# 485Driver_MAX3462.net
KiCad netlist of a schematic drawn in Altium Designer
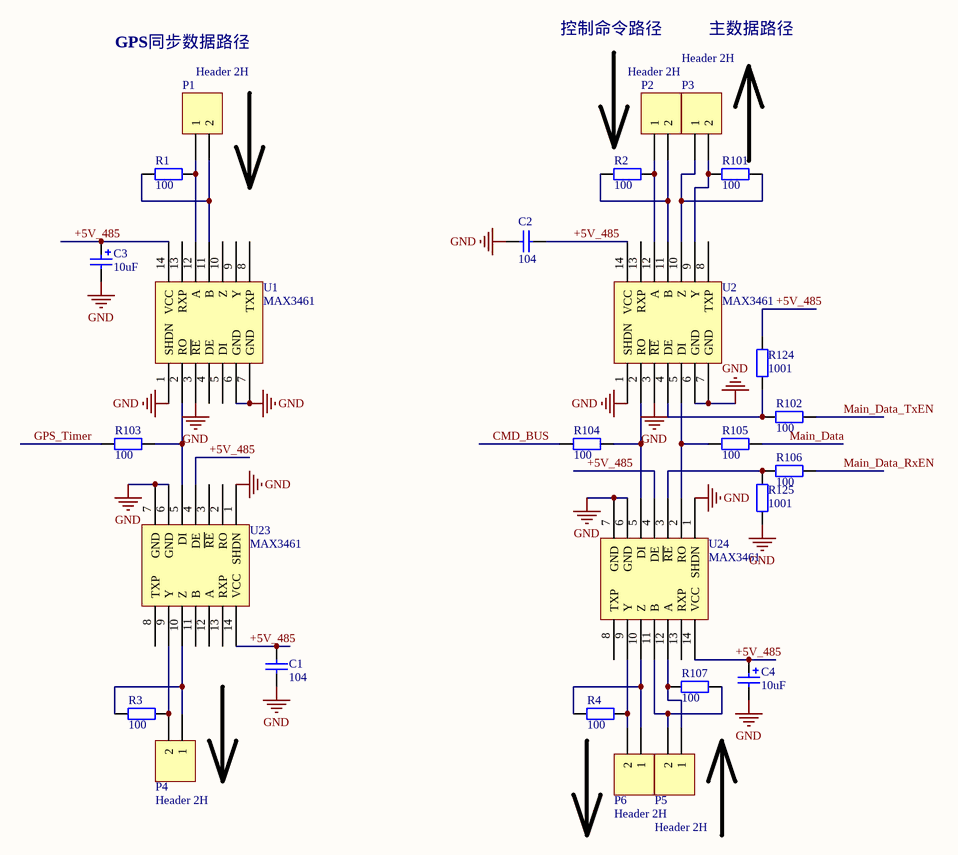
[diagram p0: 485Driver_MAX3462.SchDoc]

(export (version "E")
  (design (tool "Eeschema 10.0.6"))
  (components
    (comp (ref "C1")
      (value "104")
      (footprint "0805C")
      (description "Capacitor")
      (fields (field (name "PUBLISHER") "Altium Limited"))
      (libsource (lib "Miscellaneous Devices") (part "Cap"))
    )
    (comp (ref "C2")
      (value "104")
      (footprint "0805C")
      (description "Capacitor")
      (fields (field (name "PUBLISHER") "Altium Limited"))
      (libsource (lib "Miscellaneous Devices") (part "Cap"))
    )
    (comp (ref "C3")
      (value "10uF")
      (footprint "C68uF")
      (description "Polarized Capacitor (Axial)")
      (fields (field (name "PUBLISHER") "Altium Limited"))
      (libsource (lib "Miscellaneous Devices") (part "Cap Pol2"))
    )
    (comp (ref "C4")
      (value "10uF")
      (footprint "C68uF")
      (description "Polarized Capacitor (Axial)")
      (fields (field (name "PUBLISHER") "Altium Limited"))
      (libsource (lib "Miscellaneous Devices") (part "Cap Pol2"))
    )
    (comp (ref "P1")
      (value "Header 2H")
      (footprint "HDR1X2")
      (description "Header, 2-Pin, Right Angle")
      (fields (field (name "PUBLISHER") "Altium Limited"))
      (libsource (lib "Miscellaneous Connectors") (part "Header 2H"))
    )
    (comp (ref "P2")
      (value "Header 2H")
      (footprint "HDR1X2")
      (description "Header, 2-Pin, Right Angle")
      (fields (field (name "PUBLISHER") "Altium Limited"))
      (libsource (lib "Miscellaneous Connectors") (part "Header 2H"))
    )
    (comp (ref "P3")
      (value "Header 2H")
      (footprint "HDR1X2")
      (description "Header, 2-Pin, Right Angle")
      (fields (field (name "PUBLISHER") "Altium Limited"))
      (libsource (lib "Miscellaneous Connectors") (part "Header 2H"))
    )
    (comp (ref "P4")
      (value "Header 2H")
      (footprint "HDR1X2")
      (description "Header, 2-Pin, Right Angle")
      (fields (field (name "PUBLISHER") "Altium Limited"))
      (libsource (lib "") (part "Header 2H_1"))
    )
    (comp (ref "P5")
      (value "Header 2H")
      (footprint "HDR1X2")
      (description "Header, 2-Pin, Right Angle")
      (fields (field (name "PUBLISHER") "Altium Limited"))
      (libsource (lib "") (part "Header 2H_1"))
    )
    (comp (ref "P6")
      (value "Header 2H")
      (footprint "HDR1X2")
      (description "Header, 2-Pin, Right Angle")
      (fields (field (name "PUBLISHER") "Altium Limited"))
      (libsource (lib "") (part "Header 2H_1"))
    )
    (comp (ref "R1")
      (value "100")
      (footprint "0805R")
      (description "Resistor")
      (fields (field (name "PUBLISHER") "Altium Limited"))
      (libsource (lib "") (part "Res2_1"))
    )
    (comp (ref "R2")
      (value "100")
      (footprint "0805R")
      (description "Resistor")
      (fields (field (name "PUBLISHER") "Altium Limited"))
      (libsource (lib "") (part "Res2_1"))
    )
    (comp (ref "R3")
      (value "100")
      (footprint "0805R")
      (description "Resistor")
      (fields (field (name "PUBLISHER") "Altium Limited"))
      (libsource (lib "") (part "Res2_1"))
    )
    (comp (ref "R4")
      (value "100")
      (footprint "0805R")
      (description "Resistor")
      (fields (field (name "PUBLISHER") "Altium Limited"))
      (libsource (lib "") (part "Res2_1"))
    )
    (comp (ref "R101")
      (value "100")
      (footprint "0805R")
      (description "Resistor")
      (fields (field (name "PUBLISHER") "Altium Limited"))
      (libsource (lib "") (part "Res2_1"))
    )
    (comp (ref "R102")
      (value "100")
      (footprint "0603")
      (description "Resistor")
      (fields (field (name "PUBLISHER") "Altium Limited"))
      (libsource (lib "") (part "Res2_1"))
    )
    (comp (ref "R103")
      (value "100")
      (footprint "0603")
      (description "Resistor")
      (fields (field (name "PUBLISHER") "Altium Limited"))
      (libsource (lib "") (part "Res2_1"))
    )
    (comp (ref "R104")
      (value "100")
      (footprint "0603")
      (description "Resistor")
      (fields (field (name "PUBLISHER") "Altium Limited"))
      (libsource (lib "") (part "Res2_1"))
    )
    (comp (ref "R105")
      (value "100")
      (footprint "0603")
      (description "Resistor")
      (fields (field (name "PUBLISHER") "Altium Limited"))
      (libsource (lib "") (part "Res2_1"))
    )
    (comp (ref "R106")
      (value "100")
      (footprint "0603")
      (description "Resistor")
      (fields (field (name "PUBLISHER") "Altium Limited"))
      (libsource (lib "") (part "Res2_1"))
    )
    (comp (ref "R107")
      (value "100")
      (footprint "0805R")
      (description "Resistor")
      (fields (field (name "PUBLISHER") "Altium Limited"))
      (libsource (lib "") (part "Res2_1"))
    )
    (comp (ref "R124")
      (value "1001")
      (footprint "0603")
      (description "Resistor")
      (fields (field (name "PUBLISHER") "Altium Limited"))
      (libsource (lib "Miscellaneous Devices") (part "Res2"))
    )
    (comp (ref "R125")
      (value "1001")
      (footprint "0603")
      (description "Resistor")
      (fields (field (name "PUBLISHER") "Altium Limited"))
      (libsource (lib "Miscellaneous Devices") (part "Res2"))
    )
    (comp (ref "U1") (value "MAX3461") (footprint "SOP14") (libsource (lib "Schlib1") (part "MAX3461")))
    (comp (ref "U2") (value "MAX3461") (footprint "SOP14") (libsource (lib "Schlib1") (part "MAX3461")))
    (comp (ref "U23") (value "MAX3461") (footprint "SOP14") (libsource (lib "") (part "MAX3461_1")))
    (comp (ref "U24") (value "MAX3461") (footprint "SOP14") (libsource (lib "") (part "MAX3461_1")))
  )
  (nets
    (net (code "1") (name "/+5V_485") (class "Default")
      (node (ref "C1") (pin "2") (pinfunction "2_2") (pintype "passive"))
      (node (ref "C2") (pin "2") (pinfunction "2_2") (pintype "passive"))
      (node (ref "C3") (pin "1") (pinfunction "1_1") (pintype "passive"))
      (node (ref "C4") (pin "1") (pinfunction "1_1") (pintype "passive"))
      (node (ref "R124") (pin "1") (pinfunction "1_1") (pintype "passive"))
      (node (ref "U1") (pin "14") (pinfunction "VCC_14") (pintype "passive"))
      (node (ref "U2") (pin "14") (pinfunction "VCC_14") (pintype "passive"))
      (node (ref "U23") (pin "14") (pinfunction "VCC_14") (pintype "passive"))
      (node (ref "U23") (pin "4") (pinfunction "DE_4") (pintype "passive"))
      (node (ref "U24") (pin "14") (pinfunction "VCC_14") (pintype "passive"))
      (node (ref "U24") (pin "4") (pinfunction "DE_4") (pintype "passive"))
    )
    (net (code "2") (name "/CMD_BUS") (class "Default")
      (node (ref "R104") (pin "2") (pinfunction "2_2") (pintype "passive"))
    )
    (net (code "3") (name "/GPS_Timer") (class "Default")
      (node (ref "R103") (pin "2") (pinfunction "2_2") (pintype "passive"))
    )
    (net (code "4") (name "/Main_Data") (class "Default")
      (node (ref "R105") (pin "1") (pinfunction "1_1") (pintype "passive"))
    )
    (net (code "5") (name "/Main_Data_RxEN") (class "Default")
      (node (ref "R106") (pin "1") (pinfunction "1_1") (pintype "passive"))
    )
    (net (code "6") (name "/Main_Data_TxEN") (class "Default")
      (node (ref "R102") (pin "1") (pinfunction "1_1") (pintype "passive"))
    )
    (net (code "7") (name "GND") (class "Default")
      (node (ref "C1") (pin "1") (pinfunction "1_1") (pintype "passive"))
      (node (ref "C2") (pin "1") (pinfunction "1_1") (pintype "passive"))
      (node (ref "C3") (pin "2") (pinfunction "2_2") (pintype "passive"))
      (node (ref "C4") (pin "2") (pinfunction "2_2") (pintype "passive"))
      (node (ref "R125") (pin "2") (pinfunction "2_2") (pintype "passive"))
      (node (ref "U1") (pin "1") (pinfunction "SHDN_1") (pintype "passive"))
      (node (ref "U1") (pin "3") (pinfunction "~{RE}_3") (pintype "passive"))
      (node (ref "U1") (pin "6") (pinfunction "GND_6") (pintype "passive"))
      (node (ref "U1") (pin "7") (pinfunction "GND_7") (pintype "passive"))
      (node (ref "U2") (pin "1") (pinfunction "SHDN_1") (pintype "passive"))
      (node (ref "U2") (pin "3") (pinfunction "~{RE}_3") (pintype "passive"))
      (node (ref "U2") (pin "6") (pinfunction "GND_6") (pintype "passive"))
      (node (ref "U2") (pin "7") (pinfunction "GND_7") (pintype "passive"))
      (node (ref "U23") (pin "1") (pinfunction "SHDN_1") (pintype "passive"))
      (node (ref "U23") (pin "6") (pinfunction "GND_6") (pintype "passive"))
      (node (ref "U23") (pin "7") (pinfunction "GND_7") (pintype "passive"))
      (node (ref "U24") (pin "1") (pinfunction "SHDN_1") (pintype "passive"))
      (node (ref "U24") (pin "6") (pinfunction "GND_6") (pintype "passive"))
      (node (ref "U24") (pin "7") (pinfunction "GND_7") (pintype "passive"))
    )
    (net (code "8") (name "Net-(U1-A)") (class "Default")
      (node (ref "P1") (pin "1") (pinfunction "1_1") (pintype "passive"))
      (node (ref "R1") (pin "1") (pinfunction "1_1") (pintype "passive"))
      (node (ref "U1") (pin "12") (pinfunction "A_12") (pintype "passive"))
    )
    (net (code "9") (name "Net-(U1-B)") (class "Default")
      (node (ref "P1") (pin "2") (pinfunction "2_2") (pintype "passive"))
      (node (ref "R1") (pin "2") (pinfunction "2_2") (pintype "passive"))
      (node (ref "U1") (pin "11") (pinfunction "B_11") (pintype "passive"))
    )
    (net (code "10") (name "Net-(U1-RO)") (class "Default")
      (node (ref "R103") (pin "1") (pinfunction "1_1") (pintype "passive"))
      (node (ref "U1") (pin "2") (pinfunction "RO_2") (pintype "passive"))
      (node (ref "U23") (pin "5") (pinfunction "DI_5") (pintype "passive"))
    )
    (net (code "11") (name "Net-(U2-A)") (class "Default")
      (node (ref "P2") (pin "1") (pinfunction "1_1") (pintype "passive"))
      (node (ref "R2") (pin "1") (pinfunction "1_1") (pintype "passive"))
      (node (ref "U2") (pin "12") (pinfunction "A_12") (pintype "passive"))
    )
    (net (code "12") (name "Net-(U2-B)") (class "Default")
      (node (ref "P2") (pin "2") (pinfunction "2_2") (pintype "passive"))
      (node (ref "R2") (pin "2") (pinfunction "2_2") (pintype "passive"))
      (node (ref "U2") (pin "11") (pinfunction "B_11") (pintype "passive"))
    )
    (net (code "13") (name "Net-(U2-DE)") (class "Default")
      (node (ref "R102") (pin "2") (pinfunction "2_2") (pintype "passive"))
      (node (ref "R124") (pin "2") (pinfunction "2_2") (pintype "passive"))
      (node (ref "U2") (pin "4") (pinfunction "DE_4") (pintype "passive"))
    )
    (net (code "14") (name "Net-(U2-DI)") (class "Default")
      (node (ref "R105") (pin "2") (pinfunction "2_2") (pintype "passive"))
      (node (ref "U2") (pin "5") (pinfunction "DI_5") (pintype "passive"))
      (node (ref "U24") (pin "2") (pinfunction "RO_2") (pintype "passive"))
    )
    (net (code "15") (name "Net-(U2-RO)") (class "Default")
      (node (ref "R104") (pin "1") (pinfunction "1_1") (pintype "passive"))
      (node (ref "U2") (pin "2") (pinfunction "RO_2") (pintype "passive"))
      (node (ref "U24") (pin "5") (pinfunction "DI_5") (pintype "passive"))
    )
    (net (code "16") (name "Net-(U2-Y)") (class "Default")
      (node (ref "P3") (pin "2") (pinfunction "2_2") (pintype "passive"))
      (node (ref "R101") (pin "2") (pinfunction "2_2") (pintype "passive"))
      (node (ref "U2") (pin "9") (pinfunction "Y_9") (pintype "passive"))
    )
    (net (code "17") (name "Net-(U2-Z)") (class "Default")
      (node (ref "P3") (pin "1") (pinfunction "1_1") (pintype "passive"))
      (node (ref "R101") (pin "1") (pinfunction "1_1") (pintype "passive"))
      (node (ref "U2") (pin "10") (pinfunction "Z_10") (pintype "passive"))
    )
    (net (code "18") (name "Net-(U23-Y)") (class "Default")
      (node (ref "P4") (pin "2") (pinfunction "2_2") (pintype "passive"))
      (node (ref "R3") (pin "1") (pinfunction "1_1") (pintype "passive"))
      (node (ref "U23") (pin "9") (pinfunction "Y_9") (pintype "passive"))
    )
    (net (code "19") (name "Net-(U23-Z)") (class "Default")
      (node (ref "P4") (pin "1") (pinfunction "1_1") (pintype "passive"))
      (node (ref "R3") (pin "2") (pinfunction "2_2") (pintype "passive"))
      (node (ref "U23") (pin "10") (pinfunction "Z_10") (pintype "passive"))
    )
    (net (code "20") (name "Net-(U24-A)") (class "Default")
      (node (ref "P5") (pin "1") (pinfunction "1_1") (pintype "passive"))
      (node (ref "R107") (pin "2") (pinfunction "2_2") (pintype "passive"))
      (node (ref "U24") (pin "12") (pinfunction "A_12") (pintype "passive"))
    )
    (net (code "21") (name "Net-(U24-B)") (class "Default")
      (node (ref "P5") (pin "2") (pinfunction "2_2") (pintype "passive"))
      (node (ref "R107") (pin "1") (pinfunction "1_1") (pintype "passive"))
      (node (ref "U24") (pin "11") (pinfunction "B_11") (pintype "passive"))
    )
    (net (code "22") (name "Net-(U24-Y)") (class "Default")
      (node (ref "P6") (pin "2") (pinfunction "2_2") (pintype "passive"))
      (node (ref "R4") (pin "1") (pinfunction "1_1") (pintype "passive"))
      (node (ref "U24") (pin "9") (pinfunction "Y_9") (pintype "passive"))
    )
    (net (code "23") (name "Net-(U24-Z)") (class "Default")
      (node (ref "P6") (pin "1") (pinfunction "1_1") (pintype "passive"))
      (node (ref "R4") (pin "2") (pinfunction "2_2") (pintype "passive"))
      (node (ref "U24") (pin "10") (pinfunction "Z_10") (pintype "passive"))
    )
    (net (code "24") (name "Net-(U24-~{RE})") (class "Default")
      (node (ref "R106") (pin "2") (pinfunction "2_2") (pintype "passive"))
      (node (ref "R125") (pin "1") (pinfunction "1_1") (pintype "passive"))
      (node (ref "U24") (pin "3") (pinfunction "~{RE}_3") (pintype "passive"))
    )
    (net (code "25") (name "unconnected-(U1-DE-Pad4)") (class "Default")
      (node (ref "U1") (pin "4") (pinfunction "DE_4") (pintype "passive"))
    )
    (net (code "26") (name "unconnected-(U1-DI-Pad5)") (class "Default")
      (node (ref "U1") (pin "5") (pinfunction "DI_5") (pintype "passive"))
    )
    (net (code "27") (name "unconnected-(U1-RXP-Pad13)") (class "Default")
      (node (ref "U1") (pin "13") (pinfunction "RXP_13") (pintype "passive"))
    )
    (net (code "28") (name "unconnected-(U1-TXP-Pad8)") (class "Default")
      (node (ref "U1") (pin "8") (pinfunction "TXP_8") (pintype "passive"))
    )
    (net (code "29") (name "unconnected-(U1-Y-Pad9)") (class "Default")
      (node (ref "U1") (pin "9") (pinfunction "Y_9") (pintype "passive"))
    )
    (net (code "30") (name "unconnected-(U1-Z-Pad10)") (class "Default")
      (node (ref "U1") (pin "10") (pinfunction "Z_10") (pintype "passive"))
    )
    (net (code "31") (name "unconnected-(U2-RXP-Pad13)") (class "Default")
      (node (ref "U2") (pin "13") (pinfunction "RXP_13") (pintype "passive"))
    )
    (net (code "32") (name "unconnected-(U2-TXP-Pad8)") (class "Default")
      (node (ref "U2") (pin "8") (pinfunction "TXP_8") (pintype "passive"))
    )
    (net (code "33") (name "unconnected-(U23-A-Pad12)") (class "Default")
      (node (ref "U23") (pin "12") (pinfunction "A_12") (pintype "passive"))
    )
    (net (code "34") (name "unconnected-(U23-B-Pad11)") (class "Default")
      (node (ref "U23") (pin "11") (pinfunction "B_11") (pintype "passive"))
    )
    (net (code "35") (name "unconnected-(U23-RO-Pad2)") (class "Default")
      (node (ref "U23") (pin "2") (pinfunction "RO_2") (pintype "passive"))
    )
    (net (code "36") (name "unconnected-(U23-RXP-Pad13)") (class "Default")
      (node (ref "U23") (pin "13") (pinfunction "RXP_13") (pintype "passive"))
    )
    (net (code "37") (name "unconnected-(U23-TXP-Pad8)") (class "Default")
      (node (ref "U23") (pin "8") (pinfunction "TXP_8") (pintype "passive"))
    )
    (net (code "38") (name "unconnected-(U23-~{RE}-Pad3)") (class "Default")
      (node (ref "U23") (pin "3") (pinfunction "~{RE}_3") (pintype "passive"))
    )
    (net (code "39") (name "unconnected-(U24-RXP-Pad13)") (class "Default")
      (node (ref "U24") (pin "13") (pinfunction "RXP_13") (pintype "passive"))
    )
    (net (code "40") (name "unconnected-(U24-TXP-Pad8)") (class "Default")
      (node (ref "U24") (pin "8") (pinfunction "TXP_8") (pintype "passive"))
    )
  )
)
